# sche.net
KiCad netlist of a schematic drawn in Altium Designer
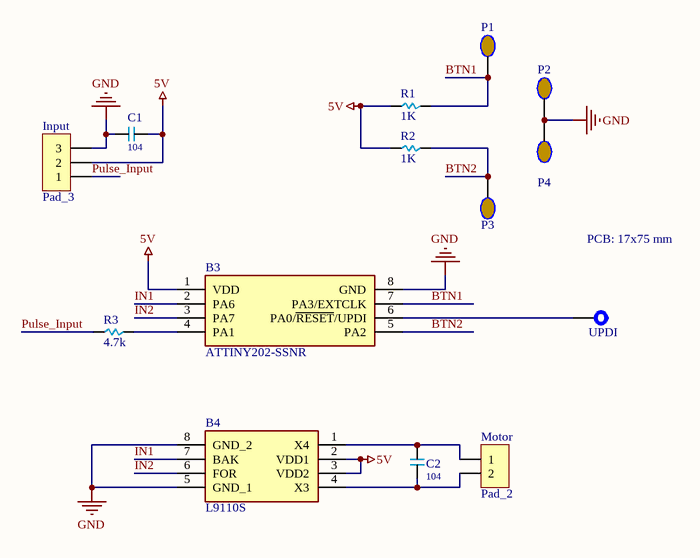
[diagram p0: sche.SchDoc]

(export (version "E")
  (design (tool "Eeschema 10.0.6"))
  (components
    (comp (ref "B3")
      (value "ATTINY202-SSNR")
      (footprint "SOIC127P600X175-8N")
      (description "8-bit Microcontrollers - MCU 20MHz, 2KB, SOIC8, Ind 105C, Green, T&R")
      (fields (field (name "MOUSER PART NUMBER") "579-ATTINY202-SSNR"))
      (libsource (lib "KM_ALTIUM") (part "ATTINY202-SSNR"))
    )
    (comp (ref "B4")
      (value "L9110S")
      (footprint "SOIC127P600X175-8N")
      (description "Motor Drivers SOP-8_150mil RoHS")
      (libsource (lib "KM_ALTIUM") (part "L9110S"))
    )
    (comp (ref "C1") (value "104") (footprint "CAP 0603") (libsource (lib "KM_ALTIUM") (part "CAP")))
    (comp (ref "C2") (value "104") (footprint "CAP 0603") (libsource (lib "KM_ALTIUM") (part "CAP")))
    (comp (ref "Input") (value "Pad_3") (footprint "Pad_3_2.54") (libsource (lib "KM_ALTIUM") (part "Pad_3")))
    (comp (ref "Motor") (value "Pad_2") (footprint "PAD_2_2.54") (libsource (lib "KM_ALTIUM") (part "Pad_2")))
    (comp (ref "P1") (value "Pad_1") (footprint "Pad_1") (libsource (lib "KM_ALTIUM") (part "Pad_1")))
    (comp (ref "P2") (value "Pad_1") (footprint "Pad_1") (libsource (lib "KM_ALTIUM") (part "Pad_1")))
    (comp (ref "P3") (value "Pad_1") (footprint "Pad_1") (libsource (lib "KM_ALTIUM") (part "Pad_1")))
    (comp (ref "P4") (value "Pad_1") (footprint "Pad_1") (libsource (lib "KM_ALTIUM") (part "Pad_1")))
    (comp (ref "R1") (value "1K") (footprint "RES 0603") (libsource (lib "KM_ALTIUM") (part "RES")))
    (comp (ref "R2") (value "1K") (footprint "RES 0603") (libsource (lib "KM_ALTIUM") (part "RES")))
    (comp (ref "R3") (value "4.7k") (footprint "RES 0603") (libsource (lib "KM_ALTIUM") (part "RES")))
    (comp (ref "UPDI") (value "TEST") (footprint "TEST") (libsource (lib "KM_ALTIUM") (part "Test_Point")))
  )
  (nets
    (net (code "1") (name "/BTN1") (class "Default")
      (node (ref "B3") (pin "7") (pinfunction "PA3/EXTCLK_7") (pintype "passive"))
      (node (ref "P1") (pin "1") (pintype "passive"))
      (node (ref "R1") (pin "2") (pinfunction "2_2") (pintype "passive"))
    )
    (net (code "2") (name "/BTN2") (class "Default")
      (node (ref "B3") (pin "5") (pinfunction "PA2_5") (pintype "passive"))
      (node (ref "P3") (pin "1") (pintype "passive"))
      (node (ref "R2") (pin "2") (pinfunction "2_2") (pintype "passive"))
    )
    (net (code "3") (name "/IN1") (class "Default")
      (node (ref "B3") (pin "2") (pinfunction "PA6_2") (pintype "passive"))
      (node (ref "B4") (pin "7") (pinfunction "BAK_7") (pintype "passive"))
    )
    (net (code "4") (name "/IN2") (class "Default")
      (node (ref "B3") (pin "3") (pinfunction "PA7_3") (pintype "passive"))
      (node (ref "B4") (pin "6") (pinfunction "FOR_6") (pintype "passive"))
    )
    (net (code "5") (name "/Pulse_Input") (class "Default")
      (node (ref "Input") (pin "1") (pinfunction "1_1") (pintype "passive"))
      (node (ref "R3") (pin "1") (pinfunction "1_1") (pintype "passive"))
    )
    (net (code "6") (name "5V") (class "Default")
      (node (ref "B3") (pin "1") (pinfunction "VDD_1") (pintype "passive"))
      (node (ref "B4") (pin "2") (pinfunction "VDD1_2") (pintype "passive"))
      (node (ref "B4") (pin "3") (pinfunction "VDD2_3") (pintype "passive"))
      (node (ref "C1") (pin "1") (pinfunction "1_1") (pintype "passive"))
      (node (ref "Input") (pin "2") (pinfunction "2_2") (pintype "passive"))
      (node (ref "R1") (pin "1") (pinfunction "1_1") (pintype "passive"))
      (node (ref "R2") (pin "1") (pinfunction "1_1") (pintype "passive"))
    )
    (net (code "7") (name "GND") (class "Default")
      (node (ref "B3") (pin "8") (pinfunction "GND_8") (pintype "passive"))
      (node (ref "B4") (pin "5") (pinfunction "GND_1_5") (pintype "passive"))
      (node (ref "B4") (pin "8") (pinfunction "GND_2_8") (pintype "passive"))
      (node (ref "C1") (pin "2") (pinfunction "2_2") (pintype "passive"))
      (node (ref "Input") (pin "3") (pinfunction "3_3") (pintype "passive"))
      (node (ref "P2") (pin "1") (pintype "passive"))
      (node (ref "P4") (pin "1") (pintype "passive"))
    )
    (net (code "8") (name "Net-(B3-PA0{slash}~{RESET}{slash}UPDI)") (class "Default")
      (node (ref "B3") (pin "6") (pinfunction "PA0/~{RESET}/UPDI_6") (pintype "passive"))
      (node (ref "UPDI") (pin "1") (pinfunction "1_1") (pintype "passive"))
    )
    (net (code "9") (name "Net-(B3-PA1)") (class "Default")
      (node (ref "B3") (pin "4") (pinfunction "PA1_4") (pintype "passive"))
      (node (ref "R3") (pin "2") (pinfunction "2_2") (pintype "passive"))
    )
    (net (code "10") (name "Net-(B4-X3)") (class "Default")
      (node (ref "B4") (pin "4") (pinfunction "X3_4") (pintype "passive"))
      (node (ref "C2") (pin "2") (pinfunction "2_2") (pintype "passive"))
      (node (ref "Motor") (pin "2") (pinfunction "2_2") (pintype "passive"))
    )
    (net (code "11") (name "Net-(B4-X4)") (class "Default")
      (node (ref "B4") (pin "1") (pinfunction "X4_1") (pintype "passive"))
      (node (ref "C2") (pin "1") (pinfunction "1_1") (pintype "passive"))
      (node (ref "Motor") (pin "1") (pinfunction "1_1") (pintype "passive"))
    )
  )
)
